# ATtiny10.net
KiCad netlist of a schematic drawn in EAGLE
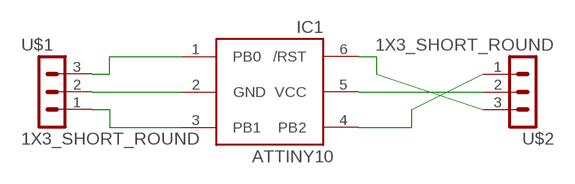
[diagram p0: schematic, sheet 1]

(export (version "E")
  (design (tool "Eeschema 10.0.6"))
  (components
    (comp (ref "IC1")
      (value "ATTINY10")
      (footprint "eagle-import:SOT23-6")
      (libsource (lib "eagle-import") (part "ATTINY10"))
    )
    (comp (ref "U$1")
      (value "1X3_SHORT_ROUND")
      (footprint "eagle-import:1X3_SHORT_ROUND")
      (libsource (lib "eagle-import") (part "1X3_SHORT_ROUND"))
    )
    (comp (ref "U$2")
      (value "1X3_SHORT_ROUND")
      (footprint "eagle-import:1X3_SHORT_ROUND")
      (libsource (lib "eagle-import") (part "1X3_SHORT_ROUND"))
    )
  )
  (nets
    (net (code "1") (name "Net-(IC1-GND)") (class "Default")
      (node (ref "IC1") (pin "2") (pinfunction "GND_2") (pintype "power_in"))
      (node (ref "U$1") (pin "2") (pinfunction "5_2") (pintype "passive"))
    )
    (net (code "2") (name "Net-(IC1-PB0)") (class "Default")
      (node (ref "IC1") (pin "1") (pinfunction "PB0_1") (pintype "bidirectional"))
      (node (ref "U$1") (pin "3") (pinfunction "6_3") (pintype "passive"))
    )
    (net (code "3") (name "Net-(IC1-PB1)") (class "Default")
      (node (ref "IC1") (pin "3") (pinfunction "PB1_3") (pintype "bidirectional"))
      (node (ref "U$1") (pin "1") (pinfunction "4_1") (pintype "passive"))
    )
    (net (code "4") (name "Net-(IC1-PB2)") (class "Default")
      (node (ref "IC1") (pin "4") (pinfunction "PB2_4") (pintype "bidirectional"))
      (node (ref "U$2") (pin "1") (pinfunction "4_1") (pintype "passive"))
    )
    (net (code "5") (name "Net-(IC1-VCC)") (class "Default")
      (node (ref "IC1") (pin "5") (pinfunction "VCC_5") (pintype "power_in"))
      (node (ref "U$2") (pin "2") (pinfunction "5_2") (pintype "passive"))
    )
    (net (code "6") (name "Net-(IC1-{slash}RST)") (class "Default")
      (node (ref "IC1") (pin "6") (pinfunction "/RST_6") (pintype "bidirectional"))
      (node (ref "U$2") (pin "3") (pinfunction "6_3") (pintype "passive"))
    )
  )
)
